# 19_SOLENOID_OF.net
KiCad netlist of a schematic drawn in Altium Designer
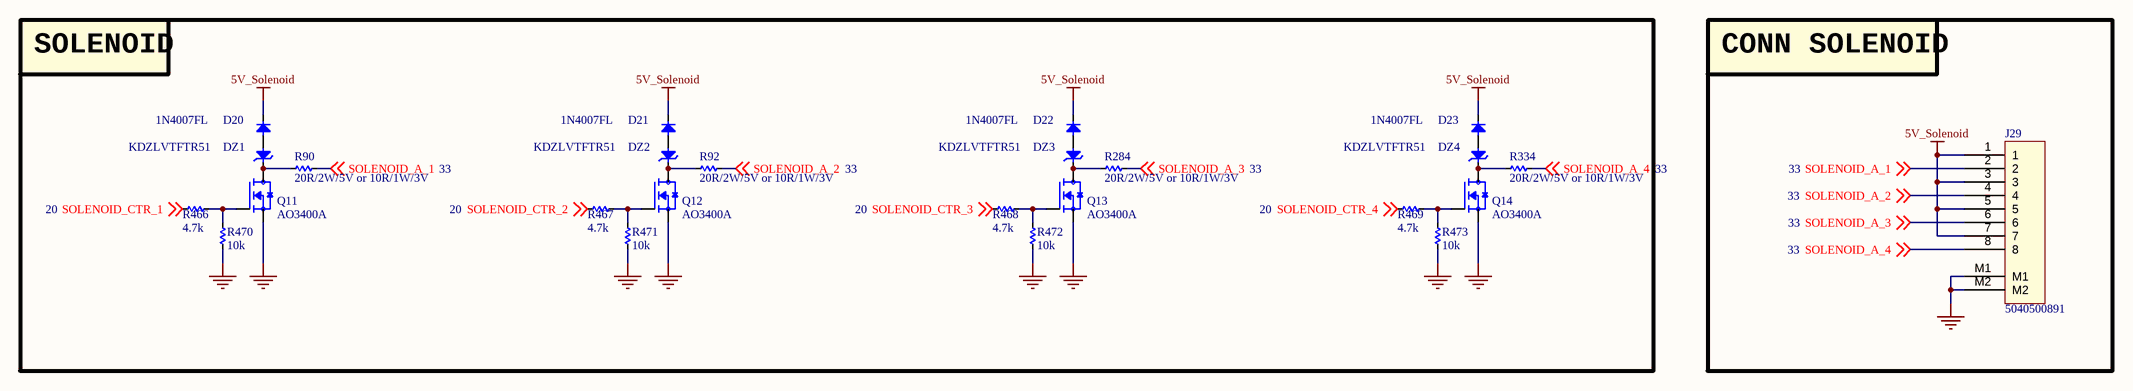
[diagram p0: 19_SOLENOID_OF.SchDoc]

(export (version "E")
  (design (tool "Eeschema 10.0.6"))
  (components
    (comp (ref "D20")
      (value "1N4007FL")
      (footprint "SOD3717X145N")
      (description "Default Diode")
      (fields (field (name "PUBLISHER") "Altium Limited"))
      (libsource (lib "LABLIB") (part "Diode SMD"))
    )
    (comp (ref "D21")
      (value "1N4007FL")
      (footprint "SOD3717X145N")
      (description "Default Diode")
      (fields (field (name "PUBLISHER") "Altium Limited"))
      (libsource (lib "LABLIB") (part "Diode SMD"))
    )
    (comp (ref "D22")
      (value "1N4007FL")
      (footprint "SOD3717X145N")
      (description "Default Diode")
      (fields (field (name "PUBLISHER") "Altium Limited"))
      (libsource (lib "LABLIB") (part "Diode SMD"))
    )
    (comp (ref "D23")
      (value "1N4007FL")
      (footprint "SOD3717X145N")
      (description "Default Diode")
      (fields (field (name "PUBLISHER") "Altium Limited"))
      (libsource (lib "LABLIB") (part "Diode SMD"))
    )
    (comp (ref "DZ1")
      (value "KDZLVTFTR51")
      (footprint "SOD3717X145N")
      (description "Zenner")
      (libsource (lib "LABLIB") (part "DIODE Zener"))
    )
    (comp (ref "DZ2")
      (value "KDZLVTFTR51")
      (footprint "SOD3717X145N")
      (description "Zenner")
      (libsource (lib "LABLIB") (part "DIODE Zener"))
    )
    (comp (ref "DZ3")
      (value "KDZLVTFTR51")
      (footprint "SOD3717X145N")
      (description "Zenner")
      (libsource (lib "LABLIB") (part "DIODE Zener"))
    )
    (comp (ref "DZ4")
      (value "KDZLVTFTR51")
      (footprint "SOD3717X145N")
      (description "Zenner")
      (libsource (lib "LABLIB") (part "DIODE Zener"))
    )
    (comp (ref "J29")
      (value "5040500891")
      (footprint "MOLEX_5040500891")
      (libsource (lib "LABLIB") (part "Header 8x1_2M"))
    )
    (comp (ref "Q11")
      (value "AO3400A")
      (footprint "SOT95P240X120-3N")
      (description "N-Channel 30 V 5.7A (Ta) 1.4W (Ta) Surface Mount SOT-23-3")
      (fields (field (name "MF") "Alpha & Omega Semiconductor"))
      (libsource (lib "LABLIB") (part "MOSFET_N"))
    )
    (comp (ref "Q12")
      (value "AO3400A")
      (footprint "SOT95P240X120-3N")
      (description "N-Channel 30 V 5.7A (Ta) 1.4W (Ta) Surface Mount SOT-23-3")
      (fields (field (name "MF") "Alpha & Omega Semiconductor"))
      (libsource (lib "LABLIB") (part "MOSFET_N"))
    )
    (comp (ref "Q13")
      (value "AO3400A")
      (footprint "SOT95P240X120-3N")
      (description "N-Channel 30 V 5.7A (Ta) 1.4W (Ta) Surface Mount SOT-23-3")
      (fields (field (name "MF") "Alpha & Omega Semiconductor"))
      (libsource (lib "LABLIB") (part "MOSFET_N"))
    )
    (comp (ref "Q14")
      (value "AO3400A")
      (footprint "SOT95P240X120-3N")
      (description "N-Channel 30 V 5.7A (Ta) 1.4W (Ta) Surface Mount SOT-23-3")
      (fields (field (name "MF") "Alpha & Omega Semiconductor"))
      (libsource (lib "LABLIB") (part "MOSFET_N"))
    )
    (comp (ref "R90")
      (value "20R/2W/5V or 10R/1W/3V")
      (footprint "RES_C_6331X65_N")
      (description "RES")
      (libsource (lib "LABLIB") (part "_RES_B_2"))
    )
    (comp (ref "R92")
      (value "20R/2W/5V or 10R/1W/3V")
      (footprint "RES_C_6331X65_N")
      (description "RES")
      (libsource (lib "LABLIB") (part "_RES_B_2"))
    )
    (comp (ref "R284")
      (value "20R/2W/5V or 10R/1W/3V")
      (footprint "RES_C_6331X65_N")
      (description "RES")
      (libsource (lib "LABLIB") (part "_RES_B_2"))
    )
    (comp (ref "R334")
      (value "20R/2W/5V or 10R/1W/3V")
      (footprint "RES_C_6331X65_N")
      (description "RES")
      (libsource (lib "LABLIB") (part "_RES_B_2"))
    )
    (comp (ref "R466")
      (value "4.7k")
      (footprint "RES_C_1005X40")
      (description "RES")
      (libsource (lib "LABLIB") (part "_RES_B_2"))
    )
    (comp (ref "R467")
      (value "4.7k")
      (footprint "RES_C_1005X40")
      (description "RES")
      (libsource (lib "LABLIB") (part "_RES_B_2"))
    )
    (comp (ref "R468")
      (value "4.7k")
      (footprint "RES_C_1005X40")
      (description "RES")
      (libsource (lib "LABLIB") (part "_RES_B_2"))
    )
    (comp (ref "R469")
      (value "4.7k")
      (footprint "RES_C_1005X40")
      (description "RES")
      (libsource (lib "LABLIB") (part "_RES_B_2"))
    )
    (comp (ref "R470")
      (value "10k")
      (footprint "RES_C_1005X40")
      (description "RES")
      (libsource (lib "LABLIB") (part "_RES_B_2"))
    )
    (comp (ref "R471")
      (value "10k")
      (footprint "RES_C_1005X40")
      (description "RES")
      (libsource (lib "LABLIB") (part "_RES_B_2"))
    )
    (comp (ref "R472")
      (value "10k")
      (footprint "RES_C_1005X40")
      (description "RES")
      (libsource (lib "LABLIB") (part "_RES_B_2"))
    )
    (comp (ref "R473")
      (value "10k")
      (footprint "RES_C_1005X40")
      (description "RES")
      (libsource (lib "LABLIB") (part "_RES_B_2"))
    )
  )
  (nets
    (net (code "1") (name "5V_Solenoid") (class "Default")
      (node (ref "D20") (pin "1") (pinfunction "K_1") (pintype "passive"))
      (node (ref "D21") (pin "1") (pinfunction "K_1") (pintype "passive"))
      (node (ref "D22") (pin "1") (pinfunction "K_1") (pintype "passive"))
      (node (ref "D23") (pin "1") (pinfunction "K_1") (pintype "passive"))
      (node (ref "J29") (pin "1") (pinfunction "1_1") (pintype "passive"))
      (node (ref "J29") (pin "3") (pinfunction "3_3") (pintype "passive"))
      (node (ref "J29") (pin "5") (pinfunction "5_5") (pintype "passive"))
      (node (ref "J29") (pin "7") (pinfunction "7_7") (pintype "passive"))
    )
    (net (code "2") (name "GND") (class "Default")
      (node (ref "J29") (pin "M1") (pinfunction "M1_M1") (pintype "passive"))
      (node (ref "J29") (pin "M2") (pinfunction "M2_M2") (pintype "passive"))
      (node (ref "Q11") (pin "2") (pinfunction "S_2") (pintype "passive"))
      (node (ref "Q12") (pin "2") (pinfunction "S_2") (pintype "passive"))
      (node (ref "Q13") (pin "2") (pinfunction "S_2") (pintype "passive"))
      (node (ref "Q14") (pin "2") (pinfunction "S_2") (pintype "passive"))
      (node (ref "R470") (pin "1") (pinfunction "1_1") (pintype "passive"))
      (node (ref "R471") (pin "1") (pinfunction "1_1") (pintype "passive"))
      (node (ref "R472") (pin "1") (pinfunction "1_1") (pintype "passive"))
      (node (ref "R473") (pin "1") (pinfunction "1_1") (pintype "passive"))
    )
    (net (code "3") (name "Net-(D20-A)") (class "Default")
      (node (ref "D20") (pin "2") (pinfunction "A_2") (pintype "passive"))
      (node (ref "DZ1") (pin "2") (pinfunction "A_2") (pintype "passive"))
    )
    (net (code "4") (name "Net-(D21-A)") (class "Default")
      (node (ref "D21") (pin "2") (pinfunction "A_2") (pintype "passive"))
      (node (ref "DZ2") (pin "2") (pinfunction "A_2") (pintype "passive"))
    )
    (net (code "5") (name "Net-(D22-A)") (class "Default")
      (node (ref "D22") (pin "2") (pinfunction "A_2") (pintype "passive"))
      (node (ref "DZ3") (pin "2") (pinfunction "A_2") (pintype "passive"))
    )
    (net (code "6") (name "Net-(D23-A)") (class "Default")
      (node (ref "D23") (pin "2") (pinfunction "A_2") (pintype "passive"))
      (node (ref "DZ4") (pin "2") (pinfunction "A_2") (pintype "passive"))
    )
    (net (code "7") (name "Net-(DZ1-K)") (class "Default")
      (node (ref "DZ1") (pin "1") (pinfunction "K_1") (pintype "passive"))
      (node (ref "Q11") (pin "3") (pinfunction "D_3") (pintype "passive"))
      (node (ref "R90") (pin "2") (pinfunction "2_2") (pintype "passive"))
    )
    (net (code "8") (name "Net-(DZ2-K)") (class "Default")
      (node (ref "DZ2") (pin "1") (pinfunction "K_1") (pintype "passive"))
      (node (ref "Q12") (pin "3") (pinfunction "D_3") (pintype "passive"))
      (node (ref "R92") (pin "2") (pinfunction "2_2") (pintype "passive"))
    )
    (net (code "9") (name "Net-(DZ3-K)") (class "Default")
      (node (ref "DZ3") (pin "1") (pinfunction "K_1") (pintype "passive"))
      (node (ref "Q13") (pin "3") (pinfunction "D_3") (pintype "passive"))
      (node (ref "R284") (pin "2") (pinfunction "2_2") (pintype "passive"))
    )
    (net (code "10") (name "Net-(DZ4-K)") (class "Default")
      (node (ref "DZ4") (pin "1") (pinfunction "K_1") (pintype "passive"))
      (node (ref "Q14") (pin "3") (pinfunction "D_3") (pintype "passive"))
      (node (ref "R334") (pin "2") (pinfunction "2_2") (pintype "passive"))
    )
    (net (code "11") (name "Net-(Q11-G)") (class "Default")
      (node (ref "Q11") (pin "1") (pinfunction "G_1") (pintype "passive"))
      (node (ref "R466") (pin "1") (pinfunction "1_1") (pintype "passive"))
      (node (ref "R470") (pin "2") (pinfunction "2_2") (pintype "passive"))
    )
    (net (code "12") (name "Net-(Q12-G)") (class "Default")
      (node (ref "Q12") (pin "1") (pinfunction "G_1") (pintype "passive"))
      (node (ref "R467") (pin "1") (pinfunction "1_1") (pintype "passive"))
      (node (ref "R471") (pin "2") (pinfunction "2_2") (pintype "passive"))
    )
    (net (code "13") (name "Net-(Q13-G)") (class "Default")
      (node (ref "Q13") (pin "1") (pinfunction "G_1") (pintype "passive"))
      (node (ref "R468") (pin "1") (pinfunction "1_1") (pintype "passive"))
      (node (ref "R472") (pin "2") (pinfunction "2_2") (pintype "passive"))
    )
    (net (code "14") (name "Net-(Q14-G)") (class "Default")
      (node (ref "Q14") (pin "1") (pinfunction "G_1") (pintype "passive"))
      (node (ref "R469") (pin "1") (pinfunction "1_1") (pintype "passive"))
      (node (ref "R473") (pin "2") (pinfunction "2_2") (pintype "passive"))
    )
    (net (code "15") (name "SOLENOID_A_1") (class "Default")
      (node (ref "J29") (pin "2") (pinfunction "2_2") (pintype "passive"))
      (node (ref "R90") (pin "1") (pinfunction "1_1") (pintype "passive"))
    )
    (net (code "16") (name "SOLENOID_A_2") (class "Default")
      (node (ref "J29") (pin "4") (pinfunction "4_4") (pintype "passive"))
      (node (ref "R92") (pin "1") (pinfunction "1_1") (pintype "passive"))
    )
    (net (code "17") (name "SOLENOID_A_3") (class "Default")
      (node (ref "J29") (pin "6") (pinfunction "6_6") (pintype "passive"))
      (node (ref "R284") (pin "1") (pinfunction "1_1") (pintype "passive"))
    )
    (net (code "18") (name "SOLENOID_A_4") (class "Default")
      (node (ref "J29") (pin "8") (pinfunction "8_8") (pintype "passive"))
      (node (ref "R334") (pin "1") (pinfunction "1_1") (pintype "passive"))
    )
    (net (code "19") (name "SOLENOID_CTR_1") (class "Default")
      (node (ref "R466") (pin "2") (pinfunction "2_2") (pintype "passive"))
    )
    (net (code "20") (name "SOLENOID_CTR_2") (class "Default")
      (node (ref "R467") (pin "2") (pinfunction "2_2") (pintype "passive"))
    )
    (net (code "21") (name "SOLENOID_CTR_3") (class "Default")
      (node (ref "R468") (pin "2") (pinfunction "2_2") (pintype "passive"))
    )
    (net (code "22") (name "SOLENOID_CTR_4") (class "Default")
      (node (ref "R469") (pin "2") (pinfunction "2_2") (pintype "passive"))
    )
  )
)
